# ServoControl.net
KiCad netlist of a schematic drawn in Altium Designer
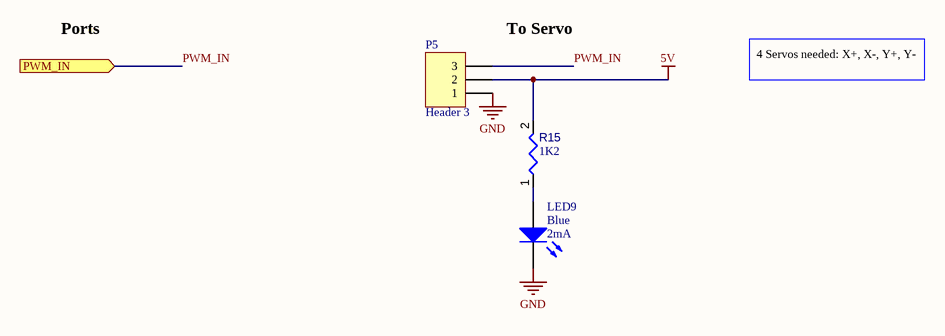
[diagram p0: ServoControl.SchDoc]

(export (version "E")
  (design (tool "Eeschema 10.0.6"))
  (components
    (comp (ref "LED9")
      (value "Blue")
      (footprint "1206_A")
      (description "KPT-3216LVVBC-D -  LED, 3.2mm x 1.6mm, Blue, SMD, 2 mA, 2.65 V, 470 nm")
      (fields
        (field (name "MANUFACTURER") "Kingbright")
        (field (name "PARTNUMBER") "KPT-3216LVVBC-D")
        (field (name "IF") "2mA")
      )
      (libsource (lib "Altium Content Vault") (part "CMP-1426-00015-1"))
    )
    (comp (ref "P5")
      (value "Header 3")
      (footprint "HDR1X3")
      (description "Header, 3-Pin")
      (fields (field (name "PUBLISHER") "Altium Limited"))
      (libsource (lib "Miscellaneous Connectors") (part "Header 3"))
    )
    (comp (ref "R15")
      (value "1K2")
      (footprint "RESC0805(2012)_L")
      (description "1K2 0.125W 5% 0805 (2012 Metric)  SMD")
      (fields (field (name "POWER") "0.125W") (field (name "TOLERANCE") "5%"))
      (libsource (lib "James Cook University") (part "1KR5J"))
    )
  )
  (nets
    (net (code "1") (name "/PWM_IN") (class "Default")
      (node (ref "P5") (pin "3") (pinfunction "3_3") (pintype "passive"))
    )
    (net (code "2") (name "5V") (class "Default")
      (node (ref "P5") (pin "2") (pinfunction "2_2") (pintype "passive"))
      (node (ref "R15") (pin "2") (pinfunction "2_2") (pintype "passive"))
    )
    (net (code "3") (name "GND") (class "Default")
      (node (ref "LED9") (pin "1") (pinfunction "K_1") (pintype "passive"))
      (node (ref "P5") (pin "1") (pinfunction "1_1") (pintype "passive"))
    )
    (net (code "4") (name "Net-(LED9-A)") (class "Default")
      (node (ref "LED9") (pin "2") (pinfunction "A_2") (pintype "passive"))
      (node (ref "R15") (pin "1") (pinfunction "1_1") (pintype "passive"))
    )
  )
)
